# P-MT3620RDB-1-7_FTDI.net
KiCad netlist of a schematic drawn in Altium Designer
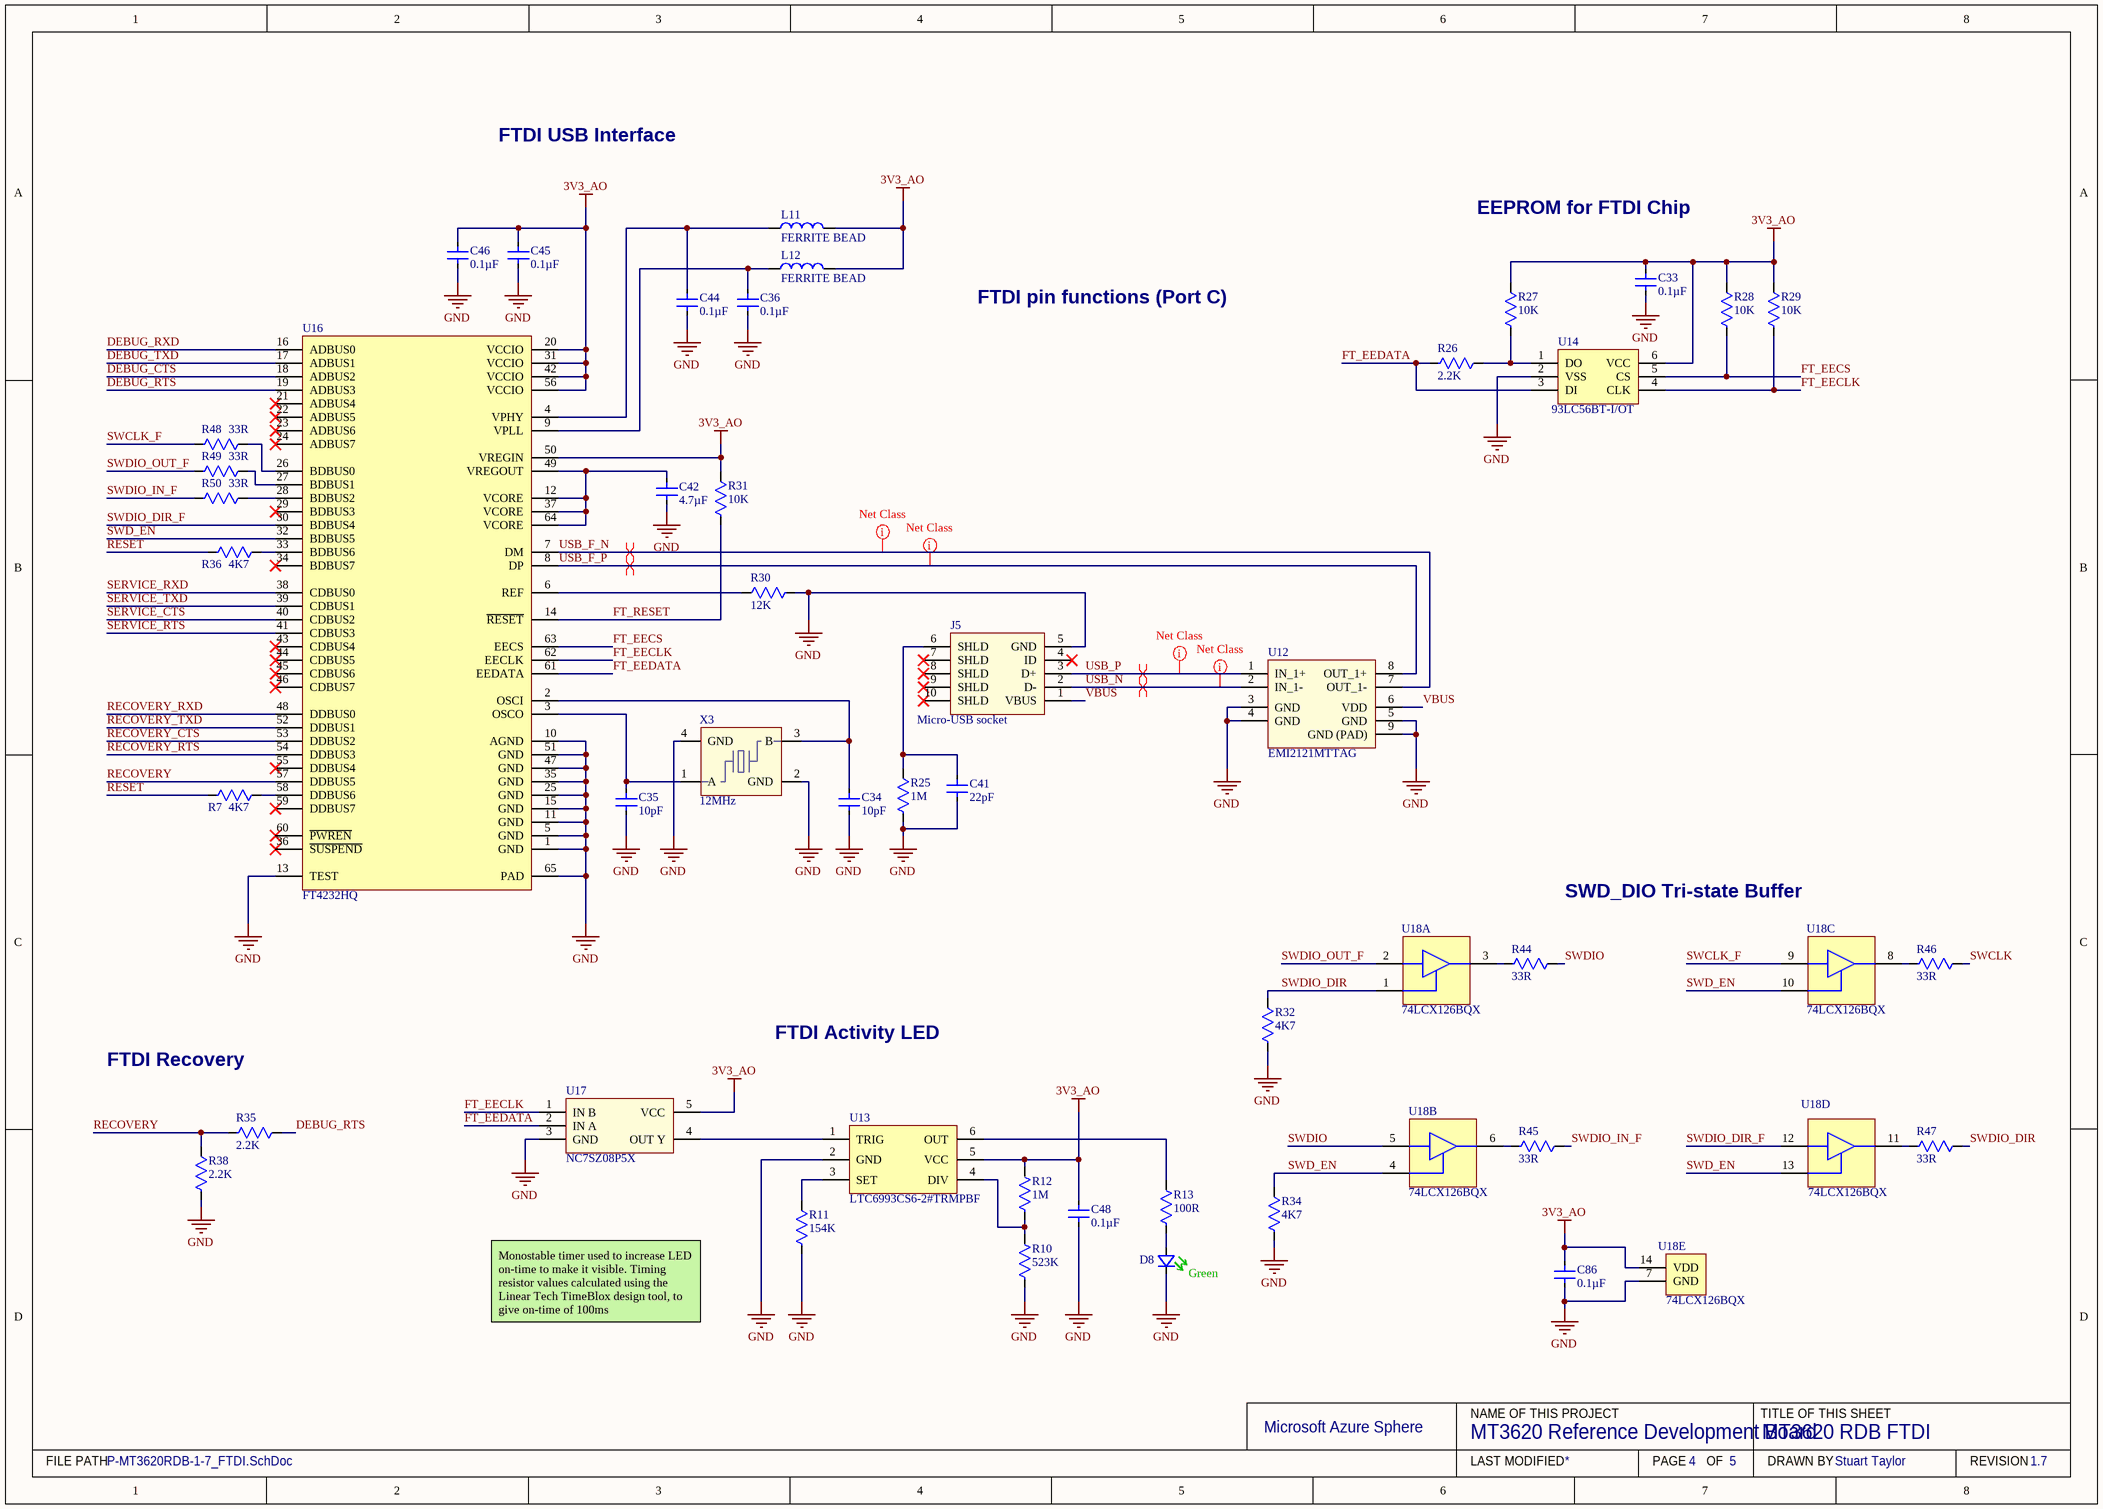
[diagram p0: P-MT3620RDB-1-7_FTDI.SchDoc]

(export (version "E")
  (design (tool "Eeschema 10.0.6"))
  (components
    (comp (ref "C33")
      (value "0.1µF")
      (footprint "CAPC1005-EIA0402 0.55MM MED")
      (description "CAP CER 0.1UF 50V 10% X7R 0402")
      (fields
        (field (name "MANUFACTURER") "TDK Corporation")
        (field (name "MANUFACTURER PART NUMBER") "C1005X7R1H104K050BB")
        (field (name "CAPACITANCE") "0.1µF")
      )
      (libsource (lib "TDK_Capacitor_C_0402") (part "0.1µF 0402 X7R 50V"))
    )
    (comp (ref "C34")
      (value "10pF")
      (footprint "CAPC1005-EIA0402 0.55MM MED")
      (description "CAP CER 10PF 50V NP0 0402")
      (fields
        (field (name "MANUFACTURER") "TDK Corporation")
        (field (name "MANUFACTURER PART NUMBER") "C1005C0G1H100D050BA")
        (field (name "CAPACITANCE") "10pF")
      )
      (libsource (lib "TDK_Capacitor_C_0402") (part "10pF 0402 C0G, NP0 50V"))
    )
    (comp (ref "C35")
      (value "10pF")
      (footprint "CAPC1005-EIA0402 0.55MM MED")
      (description "CAP CER 10PF 50V NP0 0402")
      (fields
        (field (name "MANUFACTURER") "TDK Corporation")
        (field (name "MANUFACTURER PART NUMBER") "C1005C0G1H100D050BA")
        (field (name "CAPACITANCE") "10pF")
      )
      (libsource (lib "TDK_Capacitor_C_0402") (part "10pF 0402 C0G, NP0 50V"))
    )
    (comp (ref "C36")
      (value "0.1µF")
      (footprint "CAPC1005-EIA0402 0.55MM MED")
      (description "CAP CER 0.1UF 50V 10% X7R 0402")
      (fields
        (field (name "MANUFACTURER") "TDK Corporation")
        (field (name "MANUFACTURER PART NUMBER") "C1005X7R1H104K050BB")
        (field (name "CAPACITANCE") "0.1µF")
      )
      (libsource (lib "TDK_Capacitor_C_0402") (part "0.1µF 0402 X7R 50V"))
    )
    (comp (ref "C41")
      (value "22pF")
      (footprint "CAPC1005-EIA0402 0.55MM MED")
      (description "CAP CER 22PF 50V 5% NP0 0402")
      (fields
        (field (name "MANUFACTURER") "TDK Corporation")
        (field (name "MANUFACTURER PART NUMBER") "C1005C0G1H220J050BA")
        (field (name "CAPACITANCE") "22pF")
      )
      (libsource (lib "TDK_Capacitor_C_0402") (part "22pF 0402 C0G, NP0 50V"))
    )
    (comp (ref "C42")
      (value "4.7µF")
      (footprint "CAPC1005-EIA0402 0.55MM MED")
      (description "CAP CER 4.7UF 10V 10% X5R 0402")
      (fields
        (field (name "MANUFACTURER") "TDK Corporation")
        (field (name "MANUFACTURER PART NUMBER") "C1005X5R1A475K050BC")
        (field (name "CAPACITANCE") "4.7µF")
      )
      (libsource (lib "TDK_Capacitor_C_0402") (part "4.7µF 0402 X5R 10V"))
    )
    (comp (ref "C44")
      (value "0.1µF")
      (footprint "CAPC1005-EIA0402 0.55MM MED")
      (description "CAP CER 0.1UF 50V 10% X7R 0402")
      (fields
        (field (name "MANUFACTURER") "TDK Corporation")
        (field (name "MANUFACTURER PART NUMBER") "C1005X7R1H104K050BB")
        (field (name "CAPACITANCE") "0.1µF")
      )
      (libsource (lib "TDK_Capacitor_C_0402") (part "0.1µF 0402 X7R 50V"))
    )
    (comp (ref "C45")
      (value "0.1µF")
      (footprint "CAPC1005-EIA0402 0.55MM MED")
      (description "CAP CER 0.1UF 50V 10% X7R 0402")
      (fields
        (field (name "MANUFACTURER") "TDK Corporation")
        (field (name "MANUFACTURER PART NUMBER") "C1005X7R1H104K050BB")
        (field (name "CAPACITANCE") "0.1µF")
      )
      (libsource (lib "TDK_Capacitor_C_0402") (part "0.1µF 0402 X7R 50V"))
    )
    (comp (ref "C46")
      (value "0.1µF")
      (footprint "CAPC1005-EIA0402 0.55MM MED")
      (description "CAP CER 0.1UF 50V 10% X7R 0402")
      (fields
        (field (name "MANUFACTURER") "TDK Corporation")
        (field (name "MANUFACTURER PART NUMBER") "C1005X7R1H104K050BB")
        (field (name "CAPACITANCE") "0.1µF")
      )
      (libsource (lib "TDK_Capacitor_C_0402") (part "0.1µF 0402 X7R 50V"))
    )
    (comp (ref "C48")
      (value "0.1µF")
      (footprint "CAPC1005-EIA0402 0.55MM MED")
      (description "CAP CER 0.1UF 50V 10% X7R 0402")
      (fields
        (field (name "MANUFACTURER") "TDK Corporation")
        (field (name "MANUFACTURER PART NUMBER") "C1005X7R1H104K050BB")
        (field (name "CAPACITANCE") "0.1µF")
      )
      (libsource (lib "TDK_Capacitor_C_0402") (part "0.1µF 0402 X7R 50V"))
    )
    (comp (ref "C86")
      (value "0.1µF")
      (footprint "CAPC1005-EIA0402 0.55MM MED")
      (description "CAP CER 0.1UF 50V 10% X7R 0402")
      (fields
        (field (name "MANUFACTURER") "TDK Corporation")
        (field (name "MANUFACTURER PART NUMBER") "C1005X7R1H104K050BB")
        (field (name "CAPACITANCE") "0.1µF")
      )
      (libsource (lib "TDK_Capacitor_C_0402") (part "0.1µF 0402 X7R 50V"))
    )
    (comp (ref "D8")
      (value "Green LED")
      (footprint "Rohm SML-D12 Green")
      (description "1.6 x 0.8 x 0.55mm (0603) LED 560nm Green")
      (fields
        (field (name "MANUFACTURER") "Rohm Semiconductor")
        (field (name "MANUFACTURER PART NUMBER") "SML-D12P8WT86")
        (field (name "COLOUR") "Green")
      )
      (libsource (lib "Rohm") (part "SML-D12P"))
    )
    (comp (ref "J5")
      (value "Micro-USB socket")
      (footprint "MCR-B-S-RA-SMT-CS5-T/R")
      (fields
        (field (name "MANUFACTURER") "Adam Tech")
        (field (name "MANUFACTURERS PART NUMBER") "MCR-B-S-RA-SMT-CS5-T/R")
      )
      (libsource (lib "AdamTech") (part "MCR-B-S-RA-SMT-CS5-T/R"))
    )
    (comp (ref "L11")
      (value "FERRITE BEAD")
      (footprint "CAPC1005-EIA0402 0.55MM MED")
      (description "FERRITE BEAD 120 OHM 0402 1LN")
      (fields
        (field (name "MANUFACTURER") "Murata Electronics North America")
        (field (name "MANUFACTURER PART NUMBER") "BLM15PD121SN1D")
      )
      (libsource (lib "Murata") (part "BLM15PD121SN1D"))
    )
    (comp (ref "L12")
      (value "FERRITE BEAD")
      (footprint "CAPC1005-EIA0402 0.55MM MED")
      (description "FERRITE BEAD 120 OHM 0402 1LN")
      (fields
        (field (name "MANUFACTURER") "Murata Electronics North America")
        (field (name "MANUFACTURER PART NUMBER") "BLM15PD121SN1D")
      )
      (libsource (lib "Murata") (part "BLM15PD121SN1D"))
    )
    (comp (ref "R7")
      (value "4K7")
      (footprint "RES 0402 MEDIUM DENSITY")
      (description "RES 4.7K OHM 1/10W 1% 0402 SMD")
      (fields
        (field (name "MANUFACTURER") "Panasonic Electronic Components")
        (field (name "MANUFACTURER PART NUMBER") "ERJ-2RKF4701X")
        (field (name "RESISTANCE (OHMS)") "4K7")
      )
      (libsource (lib "Panasonic_Resistor_ERJ2R") (part "4.7K"))
    )
    (comp (ref "R10")
      (value "523K")
      (footprint "RES 0402 MEDIUM DENSITY")
      (description "RES 523K OHM 1/10W 1% 0402 SMD")
      (fields
        (field (name "MANUFACTURER") "Panasonic Electronic Components")
        (field (name "MANUFACTURER PART NUMBER") "ERJ-2RKF5233X")
        (field (name "RESISTANCE (OHMS)") "523K")
      )
      (libsource (lib "Panasonic_Resistor_ERJ2R") (part "523K"))
    )
    (comp (ref "R11")
      (value "154K")
      (footprint "RES 0402 MEDIUM DENSITY")
      (description "RES 154K OHM 1/10W 1% 0402 SMD")
      (fields
        (field (name "MANUFACTURER") "Panasonic Electronic Components")
        (field (name "MANUFACTURER PART NUMBER") "ERJ-2RKF1543X")
        (field (name "RESISTANCE (OHMS)") "154K")
      )
      (libsource (lib "Panasonic_Resistor_ERJ2R") (part "154K"))
    )
    (comp (ref "R12")
      (value "1M")
      (footprint "RES 0402 MEDIUM DENSITY")
      (description "RES 1M OHM 1/10W 1% 0402 SMD")
      (fields
        (field (name "MANUFACTURER") "Panasonic Electronic Components")
        (field (name "MANUFACTURER PART NUMBER") "ERJ-2RKF1004X")
        (field (name "RESISTANCE (OHMS)") "1M")
      )
      (libsource (lib "Panasonic_Resistor_ERJ2R") (part "1M"))
    )
    (comp (ref "R13")
      (value "100R")
      (footprint "RES 0402 MEDIUM DENSITY")
      (description "RES 100 OHM 1/10W 1% 0402 SMD")
      (fields
        (field (name "MANUFACTURER") "Panasonic Electronic Components")
        (field (name "MANUFACTURER PART NUMBER") "ERJ-2RKF1000X")
        (field (name "RESISTANCE (OHMS)") "100R")
      )
      (libsource (lib "Panasonic_Resistor_ERJ2R") (part "100R"))
    )
    (comp (ref "R25")
      (value "1M")
      (footprint "RES 0402 MEDIUM DENSITY")
      (description "RES 1M OHM 1/10W 1% 0402 SMD")
      (fields
        (field (name "MANUFACTURER") "Panasonic Electronic Components")
        (field (name "MANUFACTURER PART NUMBER") "ERJ-2RKF1004X")
        (field (name "RESISTANCE (OHMS)") "1M")
      )
      (libsource (lib "Panasonic_Resistor_ERJ2R") (part "1M"))
    )
    (comp (ref "R26")
      (value "2.2K")
      (footprint "RES 0402 MEDIUM DENSITY")
      (description "RES 2.2K OHM 1/10W 1% 0402 SMD")
      (fields
        (field (name "MANUFACTURER") "Panasonic Electronic Components")
        (field (name "MANUFACTURER PART NUMBER") "ERJ-2RKF2201X")
        (field (name "RESISTANCE (OHMS)") "2.2K")
      )
      (libsource (lib "Panasonic_Resistor_ERJ2R") (part "2.2K"))
    )
    (comp (ref "R27")
      (value "10K")
      (footprint "RES 0402 MEDIUM DENSITY")
      (description "RES 10K OHM 1/10W 1% 0402 SMD")
      (fields
        (field (name "MANUFACTURER") "Panasonic Electronic Components")
        (field (name "MANUFACTURER PART NUMBER") "ERJ-2RKF1002X")
        (field (name "RESISTANCE (OHMS)") "10K")
      )
      (libsource (lib "Panasonic_Resistor_ERJ2R") (part "10K"))
    )
    (comp (ref "R28")
      (value "10K")
      (footprint "RES 0402 MEDIUM DENSITY")
      (description "RES 10K OHM 1/10W 1% 0402 SMD")
      (fields
        (field (name "MANUFACTURER") "Panasonic Electronic Components")
        (field (name "MANUFACTURER PART NUMBER") "ERJ-2RKF1002X")
        (field (name "RESISTANCE (OHMS)") "10K")
      )
      (libsource (lib "Panasonic_Resistor_ERJ2R") (part "10K"))
    )
    (comp (ref "R29")
      (value "10K")
      (footprint "RES 0402 MEDIUM DENSITY")
      (description "RES 10K OHM 1/10W 1% 0402 SMD")
      (fields
        (field (name "MANUFACTURER") "Panasonic Electronic Components")
        (field (name "MANUFACTURER PART NUMBER") "ERJ-2RKF1002X")
        (field (name "RESISTANCE (OHMS)") "10K")
      )
      (libsource (lib "Panasonic_Resistor_ERJ2R") (part "10K"))
    )
    (comp (ref "R30")
      (value "12K")
      (footprint "RES 0402 MEDIUM DENSITY")
      (description "RES 12K OHM 1/10W 1% 0402 SMD")
      (fields
        (field (name "MANUFACTURER") "Panasonic Electronic Components")
        (field (name "MANUFACTURER PART NUMBER") "ERJ-2RKF1202X")
        (field (name "RESISTANCE (OHMS)") "12K")
      )
      (libsource (lib "Panasonic_Resistor_ERJ2R") (part "12K"))
    )
    (comp (ref "R31")
      (value "10K")
      (footprint "RES 0402 MEDIUM DENSITY")
      (description "RES 10K OHM 1/10W 1% 0402 SMD")
      (fields
        (field (name "MANUFACTURER") "Panasonic Electronic Components")
        (field (name "MANUFACTURER PART NUMBER") "ERJ-2RKF1002X")
        (field (name "RESISTANCE (OHMS)") "10K")
      )
      (libsource (lib "Panasonic_Resistor_ERJ2R") (part "10K"))
    )
    (comp (ref "R32")
      (value "4K7")
      (footprint "RES 0402 MEDIUM DENSITY")
      (description "RES 4.7K OHM 1/10W 1% 0402 SMD")
      (fields
        (field (name "MANUFACTURER") "Panasonic Electronic Components")
        (field (name "MANUFACTURER PART NUMBER") "ERJ-2RKF4701X")
        (field (name "RESISTANCE (OHMS)") "4K7")
      )
      (libsource (lib "Panasonic_Resistor_ERJ2R") (part "4.7K"))
    )
    (comp (ref "R34")
      (value "4K7")
      (footprint "RES 0402 MEDIUM DENSITY")
      (description "RES 4.7K OHM 1/10W 1% 0402 SMD")
      (fields
        (field (name "MANUFACTURER") "Panasonic Electronic Components")
        (field (name "MANUFACTURER PART NUMBER") "ERJ-2RKF4701X")
        (field (name "RESISTANCE (OHMS)") "4K7")
      )
      (libsource (lib "Panasonic_Resistor_ERJ2R") (part "4.7K"))
    )
    (comp (ref "R35")
      (value "2.2K")
      (footprint "RES 0402 MEDIUM DENSITY")
      (description "RES 2.2K OHM 1/10W 1% 0402 SMD")
      (fields
        (field (name "MANUFACTURER") "Panasonic Electronic Components")
        (field (name "MANUFACTURER PART NUMBER") "ERJ-2RKF2201X")
        (field (name "RESISTANCE (OHMS)") "2.2K")
      )
      (libsource (lib "Panasonic_Resistor_ERJ2R") (part "2.2K"))
    )
    (comp (ref "R36")
      (value "4K7")
      (footprint "RES 0402 MEDIUM DENSITY")
      (description "RES 4.7K OHM 1/10W 1% 0402 SMD")
      (fields
        (field (name "MANUFACTURER") "Panasonic Electronic Components")
        (field (name "MANUFACTURER PART NUMBER") "ERJ-2RKF4701X")
        (field (name "RESISTANCE (OHMS)") "4K7")
      )
      (libsource (lib "Panasonic_Resistor_ERJ2R") (part "4.7K"))
    )
    (comp (ref "R38")
      (value "2.2K")
      (footprint "RES 0402 MEDIUM DENSITY")
      (description "RES 2.2K OHM 1/10W 1% 0402 SMD")
      (fields
        (field (name "MANUFACTURER") "Panasonic Electronic Components")
        (field (name "MANUFACTURER PART NUMBER") "ERJ-2RKF2201X")
        (field (name "RESISTANCE (OHMS)") "2.2K")
      )
      (libsource (lib "Panasonic_Resistor_ERJ2R") (part "2.2K"))
    )
    (comp (ref "R44")
      (value "33R")
      (footprint "RES 0402 MEDIUM DENSITY")
      (description "RES 33 OHM 1/10W 1% 0402 SMD")
      (fields
        (field (name "MANUFACTURER") "Panasonic Electronic Components")
        (field (name "MANUFACTURER PART NUMBER") "ERJ-2RKF33R0X")
        (field (name "RESISTANCE (OHMS)") "33R")
      )
      (libsource (lib "Panasonic_Resistor_ERJ2R") (part "33R"))
    )
    (comp (ref "R45")
      (value "33R")
      (footprint "RES 0402 MEDIUM DENSITY")
      (description "RES 33 OHM 1/10W 1% 0402 SMD")
      (fields
        (field (name "MANUFACTURER") "Panasonic Electronic Components")
        (field (name "MANUFACTURER PART NUMBER") "ERJ-2RKF33R0X")
        (field (name "RESISTANCE (OHMS)") "33R")
      )
      (libsource (lib "Panasonic_Resistor_ERJ2R") (part "33R"))
    )
    (comp (ref "R46")
      (value "33R")
      (footprint "RES 0402 MEDIUM DENSITY")
      (description "RES 33 OHM 1/10W 1% 0402 SMD")
      (fields
        (field (name "MANUFACTURER") "Panasonic Electronic Components")
        (field (name "MANUFACTURER PART NUMBER") "ERJ-2RKF33R0X")
        (field (name "RESISTANCE (OHMS)") "33R")
      )
      (libsource (lib "Panasonic_Resistor_ERJ2R") (part "33R"))
    )
    (comp (ref "R47")
      (value "33R")
      (footprint "RES 0402 MEDIUM DENSITY")
      (description "RES 33 OHM 1/10W 1% 0402 SMD")
      (fields
        (field (name "MANUFACTURER") "Panasonic Electronic Components")
        (field (name "MANUFACTURER PART NUMBER") "ERJ-2RKF33R0X")
        (field (name "RESISTANCE (OHMS)") "33R")
      )
      (libsource (lib "Panasonic_Resistor_ERJ2R") (part "33R"))
    )
    (comp (ref "R48")
      (value "33R")
      (footprint "RES 0402 MEDIUM DENSITY")
      (description "RES 33 OHM 1/10W 1% 0402 SMD")
      (fields
        (field (name "MANUFACTURER") "Panasonic Electronic Components")
        (field (name "MANUFACTURER PART NUMBER") "ERJ-2RKF33R0X")
        (field (name "RESISTANCE (OHMS)") "33R")
      )
      (libsource (lib "Panasonic_Resistor_ERJ2R") (part "33R"))
    )
    (comp (ref "R49")
      (value "33R")
      (footprint "RES 0402 MEDIUM DENSITY")
      (description "RES 33 OHM 1/10W 1% 0402 SMD")
      (fields
        (field (name "MANUFACTURER") "Panasonic Electronic Components")
        (field (name "MANUFACTURER PART NUMBER") "ERJ-2RKF33R0X")
        (field (name "RESISTANCE (OHMS)") "33R")
      )
      (libsource (lib "Panasonic_Resistor_ERJ2R") (part "33R"))
    )
    (comp (ref "R50")
      (value "33R")
      (footprint "RES 0402 MEDIUM DENSITY")
      (description "RES 33 OHM 1/10W 1% 0402 SMD")
      (fields
        (field (name "MANUFACTURER") "Panasonic Electronic Components")
        (field (name "MANUFACTURER PART NUMBER") "ERJ-2RKF33R0X")
        (field (name "RESISTANCE (OHMS)") "33R")
      )
      (libsource (lib "Panasonic_Resistor_ERJ2R") (part "33R"))
    )
    (comp (ref "U12")
      (value "EMI2121MTTAG")
      (footprint "EMI2121MTTAG")
      (description "IC FILTER COMMON MODE ESD 8WDFN")
      (fields (field (name "MANUFACTURER") "ON Semiconductor"))
      (libsource (lib "OnSemiconductor") (part "EMI2121MTTAG"))
    )
    (comp (ref "U13")
      (value "LTC6993CS6-2#TRMPBF")
      (footprint "LTC6993CS6-2#TRMPBF")
      (description "LINEAR TECHNOLOGY - LTC6993CS6-2#TRMPBF - GENERATOR, PULSE, TIMERBLOX, 6SOT-23")
      (fields (field (name "MANUFACTURER") "LINEAR TECHNOLOGY"))
      (libsource (lib "LinearTech") (part "LTC6993CS6-2#TRMPBF"))
    )
    (comp (ref "U14")
      (value "93LC56BT-I/OT")
      (footprint "SOT23-93C56B")
      (description "IC EEPROM 2KBIT 2MHZ SOT23-6")
      (fields (field (name "MANUFACTURER") "Microchip Technology"))
      (libsource (lib "Microchip") (part "93LC56BT-I/OT"))
    )
    (comp (ref "U16")
      (value "FT4232HQ")
      (footprint "FTDI_TF4232HQ_64QFN")
      (description "IC USB HS QUAD UART/SYNC 64-QFN")
      (fields
        (field (name "MANUFACTURER") "FTDI, Future Technology Devices International Ltd")
        (field (name "MANUFACTURER PART NUMBER") "FT4232HQ-REEL")
      )
      (libsource (lib "FTDI") (part "FT4232HQ"))
    )
    (comp (ref "U17")
      (value "NC7SZ08P5X")
      (footprint "SC-70-5")
      (description "IC GATE AND 1CH 2-INP SC-70-5")
      (fields (field (name "MANUFACTURER") "Fairchild Semiconductor"))
      (libsource (lib "OnSemiconductor") (part "NC7SZ08P5X"))
    )
    (comp (ref "U18")
      (value "74LCX126BQX")
      (footprint "74LCX126BQX")
      (description "IC BUFFER QUAD LV N-INV 14DQFN")
      (fields (field (name "MANUFACTURER") "Fairchild Semiconductor"))
      (libsource (lib "OnSemiconductor") (part "74LCX126BQX"))
    )
    (comp (ref "X3")
      (value "12MHz")
      (footprint "TXC 8Z")
      (description "CRYSTAL 12.000 MHZ 18PF SMD")
      (fields
        (field (name "MANUFACTURER") "TXC CORPORATION")
        (field (name "MANUFACTURER PART NUMBER") "8Z-12.000MAAJ-T")
        (field (name "FREQUENCY") "12MHz")
      )
      (libsource (lib "crystal") (part "CRYSTAL 12MHz 18pF SMD"))
    )
  )
  (nets
    (net (code "1") (name "/DEBUG_CTS") (class "Default")
      (node (ref "U16") (pin "18") (pinfunction "ADBUS2_18") (pintype "passive"))
    )
    (net (code "2") (name "/DEBUG_RTS") (class "Default")
      (node (ref "R35") (pin "1") (pinfunction "1_1") (pintype "passive"))
      (node (ref "U16") (pin "19") (pinfunction "ADBUS3_19") (pintype "passive"))
    )
    (net (code "3") (name "/DEBUG_RXD") (class "Default")
      (node (ref "U16") (pin "16") (pinfunction "ADBUS0_16") (pintype "passive"))
    )
    (net (code "4") (name "/DEBUG_TXD") (class "Default")
      (node (ref "U16") (pin "17") (pinfunction "ADBUS1_17") (pintype "passive"))
    )
    (net (code "5") (name "/FT_EECLK") (class "Default")
      (node (ref "R29") (pin "2") (pinfunction "2_2") (pintype "passive"))
      (node (ref "U14") (pin "4") (pinfunction "CLK_4") (pintype "passive"))
      (node (ref "U16") (pin "62") (pinfunction "EECLK_62") (pintype "passive"))
      (node (ref "U17") (pin "1") (pinfunction "IN_B_1") (pintype "passive"))
    )
    (net (code "6") (name "/FT_EECS") (class "Default")
      (node (ref "R28") (pin "2") (pinfunction "2_2") (pintype "passive"))
      (node (ref "U14") (pin "5") (pinfunction "CS_5") (pintype "passive"))
      (node (ref "U16") (pin "63") (pinfunction "EECS_63") (pintype "passive"))
    )
    (net (code "7") (name "/FT_EEDATA") (class "Default")
      (node (ref "R26") (pin "2") (pinfunction "2_2") (pintype "passive"))
      (node (ref "U14") (pin "3") (pinfunction "DI_3") (pintype "passive"))
      (node (ref "U16") (pin "61") (pinfunction "EEDATA_61") (pintype "passive"))
      (node (ref "U17") (pin "2") (pinfunction "IN_A_2") (pintype "passive"))
    )
    (net (code "8") (name "/FT_RESET") (class "Default")
      (node (ref "R31") (pin "2") (pinfunction "2_2") (pintype "passive"))
      (node (ref "U16") (pin "14") (pinfunction "~{RESET}_14") (pintype "passive"))
    )
    (net (code "9") (name "/RECOVERY") (class "Default")
      (node (ref "R35") (pin "2") (pinfunction "2_2") (pintype "passive"))
      (node (ref "R38") (pin "1") (pinfunction "1_1") (pintype "passive"))
      (node (ref "U16") (pin "57") (pinfunction "DDBUS5_57") (pintype "passive"))
    )
    (net (code "10") (name "/RECOVERY_CTS") (class "Default")
      (node (ref "U16") (pin "53") (pinfunction "DDBUS2_53") (pintype "passive"))
    )
    (net (code "11") (name "/RECOVERY_RTS") (class "Default")
      (node (ref "U16") (pin "54") (pinfunction "DDBUS3_54") (pintype "passive"))
    )
    (net (code "12") (name "/RECOVERY_RXD") (class "Default")
      (node (ref "U16") (pin "48") (pinfunction "DDBUS0_48") (pintype "passive"))
    )
    (net (code "13") (name "/RECOVERY_TXD") (class "Default")
      (node (ref "U16") (pin "52") (pinfunction "DDBUS1_52") (pintype "passive"))
    )
    (net (code "14") (name "/RESET") (class "Default")
      (node (ref "R36") (pin "2") (pinfunction "2_2") (pintype "passive"))
      (node (ref "R7") (pin "2") (pinfunction "2_2") (pintype "passive"))
    )
    (net (code "15") (name "/SERVICE_CTS") (class "Default")
      (node (ref "U16") (pin "40") (pinfunction "CDBUS2_40") (pintype "passive"))
    )
    (net (code "16") (name "/SERVICE_RTS") (class "Default")
      (node (ref "U16") (pin "41") (pinfunction "CDBUS3_41") (pintype "passive"))
    )
    (net (code "17") (name "/SERVICE_RXD") (class "Default")
      (node (ref "U16") (pin "38") (pinfunction "CDBUS0_38") (pintype "passive"))
    )
    (net (code "18") (name "/SERVICE_TXD") (class "Default")
      (node (ref "U16") (pin "39") (pinfunction "CDBUS1_39") (pintype "passive"))
    )
    (net (code "19") (name "/SWCLK") (class "Default")
      (node (ref "R46") (pin "1") (pinfunction "1_1") (pintype "passive"))
    )
    (net (code "20") (name "/SWCLK_F") (class "Default")
      (node (ref "R48") (pin "2") (pinfunction "2_2") (pintype "passive"))
      (node (ref "U18") (pin "9") (pinfunction "3A_9") (pintype "passive"))
    )
    (net (code "21") (name "/SWDIO") (class "Default")
      (node (ref "R44") (pin "1") (pinfunction "1_1") (pintype "passive"))
      (node (ref "U18") (pin "5") (pinfunction "2A_5") (pintype "passive"))
    )
    (net (code "22") (name "/SWDIO_DIR") (class "Default")
      (node (ref "R32") (pin "1") (pinfunction "1_1") (pintype "passive"))
      (node (ref "R47") (pin "1") (pinfunction "1_1") (pintype "passive"))
      (node (ref "U18") (pin "1") (pinfunction "1OE_1") (pintype "passive"))
    )
    (net (code "23") (name "/SWDIO_DIR_F") (class "Default")
      (node (ref "U16") (pin "30") (pinfunction "BDBUS4_30") (pintype "passive"))
      (node (ref "U18") (pin "12") (pinfunction "4A_12") (pintype "passive"))
    )
    (net (code "24") (name "/SWDIO_IN_F") (class "Default")
      (node (ref "R45") (pin "1") (pinfunction "1_1") (pintype "passive"))
      (node (ref "R50") (pin "2") (pinfunction "2_2") (pintype "passive"))
    )
    (net (code "25") (name "/SWDIO_OUT_F") (class "Default")
      (node (ref "R49") (pin "2") (pinfunction "2_2") (pintype "passive"))
      (node (ref "U18") (pin "2") (pinfunction "1A_2") (pintype "passive"))
    )
    (net (code "26") (name "/SWD_EN") (class "Default")
      (node (ref "R34") (pin "1") (pinfunction "1_1") (pintype "passive"))
      (node (ref "U16") (pin "32") (pinfunction "BDBUS5_32") (pintype "passive"))
      (node (ref "U18") (pin "10") (pinfunction "3OE_10") (pintype "passive"))
      (node (ref "U18") (pin "13") (pinfunction "4OE_13") (pintype "passive"))
      (node (ref "U18") (pin "4") (pinfunction "2OE_4") (pintype "passive"))
    )
    (net (code "27") (name "/USB_F_N") (class "Default")
      (node (ref "U12") (pin "7") (pinfunction "OUT_1-_7") (pintype "passive"))
      (node (ref "U16") (pin "7") (pinfunction "DM_7") (pintype "passive"))
    )
    (net (code "28") (name "/USB_F_P") (class "Default")
      (node (ref "U12") (pin "8") (pinfunction "OUT_1+_8") (pintype "passive"))
      (node (ref "U16") (pin "8") (pinfunction "DP_8") (pintype "passive"))
    )
    (net (code "29") (name "/USB_N") (class "Default")
      (node (ref "J5") (pin "2") (pinfunction "D-_2") (pintype "passive"))
      (node (ref "U12") (pin "2") (pinfunction "IN_1-_2") (pintype "passive"))
    )
    (net (code "30") (name "/USB_P") (class "Default")
      (node (ref "J5") (pin "3") (pinfunction "D+_3") (pintype "passive"))
      (node (ref "U12") (pin "1") (pinfunction "IN_1+_1") (pintype "passive"))
    )
    (net (code "31") (name "/VBUS") (class "Default")
      (node (ref "J5") (pin "1") (pinfunction "VBUS_1") (pintype "passive"))
      (node (ref "U12") (pin "6") (pinfunction "VDD_6") (pintype "passive"))
    )
    (net (code "32") (name "3V3_AO") (class "Default")
      (node (ref "C33") (pin "2") (pinfunction "2_2") (pintype "passive"))
      (node (ref "C45") (pin "2") (pinfunction "2_2") (pintype "passive"))
      (node (ref "C46") (pin "2") (pinfunction "2_2") (pintype "passive"))
      (node (ref "C48") (pin "2") (pinfunction "2_2") (pintype "passive"))
      (node (ref "C86") (pin "2") (pinfunction "2_2") (pintype "passive"))
      (node (ref "L11") (pin "2") (pinfunction "2_2") (pintype "passive"))
      (node (ref "L12") (pin "2") (pinfunction "2_2") (pintype "passive"))
      (node (ref "R12") (pin "1") (pinfunction "1_1") (pintype "passive"))
      (node (ref "R27") (pin "1") (pinfunction "1_1") (pintype "passive"))
      (node (ref "R28") (pin "1") (pinfunction "1_1") (pintype "passive"))
      (node (ref "R29") (pin "1") (pinfunction "1_1") (pintype "passive"))
      (node (ref "R31") (pin "1") (pinfunction "1_1") (pintype "passive"))
      (node (ref "U13") (pin "5") (pinfunction "VCC_5") (pintype "passive"))
      (node (ref "U14") (pin "6") (pinfunction "VCC_6") (pintype "passive"))
      (node (ref "U16") (pin "20") (pinfunction "VCCIO_20") (pintype "passive"))
      (node (ref "U16") (pin "31") (pinfunction "VCCIO_31") (pintype "passive"))
      (node (ref "U16") (pin "42") (pinfunction "VCCIO_42") (pintype "passive"))
      (node (ref "U16") (pin "50") (pinfunction "VREGIN_50") (pintype "passive"))
      (node (ref "U16") (pin "56") (pinfunction "VCCIO_56") (pintype "passive"))
      (node (ref "U17") (pin "5") (pinfunction "VCC_5") (pintype "passive"))
      (node (ref "U18") (pin "14") (pinfunction "VDD_14") (pintype "passive"))
    )
    (net (code "33") (name "GND") (class "Default")
      (node (ref "C33") (pin "1") (pinfunction "1_1") (pintype "passive"))
      (node (ref "C34") (pin "1") (pinfunction "1_1") (pintype "passive"))
      (node (ref "C35") (pin "1") (pinfunction "1_1") (pintype "passive"))
      (node (ref "C36") (pin "1") (pinfunction "1_1") (pintype "passive"))
      (node (ref "C41") (pin "1") (pinfunction "1_1") (pintype "passive"))
      (node (ref "C42") (pin "1") (pinfunction "1_1") (pintype "passive"))
      (node (ref "C44") (pin "1") (pinfunction "1_1") (pintype "passive"))
      (node (ref "C45") (pin "1") (pinfunction "1_1") (pintype "passive"))
      (node (ref "C46") (pin "1") (pinfunction "1_1") (pintype "passive"))
      (node (ref "C48") (pin "1") (pinfunction "1_1") (pintype "passive"))
      (node (ref "C86") (pin "1") (pinfunction "1_1") (pintype "passive"))
      (node (ref "D8") (pin "1") (pinfunction "K_1") (pintype "passive"))
      (node (ref "J5") (pin "5") (pinfunction "GND_5") (pintype "passive"))
      (node (ref "R10") (pin "2") (pinfunction "2_2") (pintype "passive"))
      (node (ref "R11") (pin "2") (pinfunction "2_2") (pintype "passive"))
      (node (ref "R25") (pin "2") (pinfunction "2_2") (pintype "passive"))
      (node (ref "R30") (pin "2") (pinfunction "2_2") (pintype "passive"))
      (node (ref "R32") (pin "2") (pinfunction "2_2") (pintype "passive"))
      (node (ref "R34") (pin "2") (pinfunction "2_2") (pintype "passive"))
      (node (ref "R38") (pin "2") (pinfunction "2_2") (pintype "passive"))
      (node (ref "U12") (pin "3") (pinfunction "GND_3") (pintype "passive"))
      (node (ref "U12") (pin "4") (pinfunction "GND_4") (pintype "passive"))
      (node (ref "U12") (pin "5") (pinfunction "GND_5") (pintype "passive"))
      (node (ref "U12") (pin "9") (pinfunction "GND_(PAD)_9") (pintype "passive"))
      (node (ref "U13") (pin "2") (pinfunction "GND_2") (pintype "passive"))
      (node (ref "U14") (pin "2") (pinfunction "VSS_2") (pintype "passive"))
      (node (ref "U16") (pin "1") (pinfunction "GND_1") (pintype "passive"))
      (node (ref "U16") (pin "10") (pinfunction "AGND_10") (pintype "passive"))
      (node (ref "U16") (pin "11") (pinfunction "GND_11") (pintype "passive"))
      (node (ref "U16") (pin "13") (pinfunction "TEST_13") (pintype "passive"))
      (node (ref "U16") (pin "15") (pinfunction "GND_15") (pintype "passive"))
      (node (ref "U16") (pin "25") (pinfunction "GND_25") (pintype "passive"))
      (node (ref "U16") (pin "35") (pinfunction "GND_35") (pintype "passive"))
      (node (ref "U16") (pin "47") (pinfunction "GND_47") (pintype "passive"))
      (node (ref "U16") (pin "5") (pinfunction "GND_5") (pintype "passive"))
      (node (ref "U16") (pin "51") (pinfunction "GND_51") (pintype "passive"))
      (node (ref "U16") (pin "65") (pinfunction "PAD_65") (pintype "passive"))
      (node (ref "U17") (pin "3") (pinfunction "GND_3") (pintype "passive"))
      (node (ref "U18") (pin "7") (pinfunction "GND_7") (pintype "passive"))
      (node (ref "X3") (pin "2") (pinfunction "GND_2") (pintype "passive"))
      (node (ref "X3") (pin "4") (pinfunction "GND_4") (pintype "passive"))
    )
    (net (code "34") (name "Net-(C41-Pad2)") (class "Default")
      (node (ref "C41") (pin "2") (pinfunction "2_2") (pintype "passive"))
      (node (ref "J5") (pin "6") (pinfunction "SHLD_6") (pintype "passive"))
      (node (ref "R25") (pin "1") (pinfunction "1_1") (pintype "passive"))
    )
    (net (code "35") (name "Net-(D8-A)") (class "Default")
      (node (ref "D8") (pin "2") (pinfunction "A_2") (pintype "passive"))
      (node (ref "R13") (pin "2") (pinfunction "2_2") (pintype "passive"))
    )
    (net (code "36") (name "Net-(U13-DIV)") (class "Default")
      (node (ref "R10") (pin "1") (pinfunction "1_1") (pintype "passive"))
      (node (ref "R12") (pin "2") (pinfunction "2_2") (pintype "passive"))
      (node (ref "U13") (pin "4") (pinfunction "DIV_4") (pintype "passive"))
    )
    (net (code "37") (name "Net-(U13-OUT)") (class "Default")
      (node (ref "R13") (pin "1") (pinfunction "1_1") (pintype "passive"))
      (node (ref "U13") (pin "6") (pinfunction "OUT_6") (pintype "passive"))
    )
    (net (code "38") (name "Net-(U13-SET)") (class "Default")
      (node (ref "R11") (pin "1") (pinfunction "1_1") (pintype "passive"))
      (node (ref "U13") (pin "3") (pinfunction "SET_3") (pintype "passive"))
    )
    (net (code "39") (name "Net-(U13-TRIG)") (class "Default")
      (node (ref "U13") (pin "1") (pinfunction "TRIG_1") (pintype "passive"))
      (node (ref "U17") (pin "4") (pinfunction "OUT_Y_4") (pintype "passive"))
    )
    (net (code "40") (name "Net-(U14-DO)") (class "Default")
      (node (ref "R26") (pin "1") (pinfunction "1_1") (pintype "passive"))
      (node (ref "R27") (pin "2") (pinfunction "2_2") (pintype "passive"))
      (node (ref "U14") (pin "1") (pinfunction "DO_1") (pintype "passive"))
    )
    (net (code "41") (name "Net-(U16-BDBUS0)") (class "Default")
      (node (ref "R48") (pin "1") (pinfunction "1_1") (pintype "passive"))
      (node (ref "U16") (pin "26") (pinfunction "BDBUS0_26") (pintype "passive"))
    )
    (net (code "42") (name "Net-(U16-BDBUS1)") (class "Default")
      (node (ref "R49") (pin "1") (pinfunction "1_1") (pintype "passive"))
      (node (ref "U16") (pin "27") (pinfunction "BDBUS1_27") (pintype "passive"))
    )
    (net (code "43") (name "Net-(U16-BDBUS2)") (class "Default")
      (node (ref "R50") (pin "1") (pinfunction "1_1") (pintype "passive"))
      (node (ref "U16") (pin "28") (pinfunction "BDBUS2_28") (pintype "passive"))
    )
    (net (code "44") (name "Net-(U16-BDBUS6)") (class "Default")
      (node (ref "R36") (pin "1") (pinfunction "1_1") (pintype "passive"))
      (node (ref "U16") (pin "33") (pinfunction "BDBUS6_33") (pintype "passive"))
    )
    (net (code "45") (name "Net-(U16-DDBUS6)") (class "Default")
      (node (ref "R7") (pin "1") (pinfunction "1_1") (pintype "passive"))
      (node (ref "U16") (pin "58") (pinfunction "DDBUS6_58") (pintype "passive"))
    )
    (net (code "46") (name "Net-(U16-OSCI)") (class "Default")
      (node (ref "C34") (pin "2") (pinfunction "2_2") (pintype "passive"))
      (node (ref "U16") (pin "2") (pinfunction "OSCI_2") (pintype "passive"))
      (node (ref "X3") (pin "3") (pinfunction "B_3") (pintype "passive"))
    )
    (net (code "47") (name "Net-(U16-OSCO)") (class "Default")
      (node (ref "C35") (pin "2") (pinfunction "2_2") (pintype "passive"))
      (node (ref "U16") (pin "3") (pinfunction "OSCO_3") (pintype "passive"))
      (node (ref "X3") (pin "1") (pinfunction "A_1") (pintype "passive"))
    )
    (net (code "48") (name "Net-(U16-REF)") (class "Default")
      (node (ref "R30") (pin "1") (pinfunction "1_1") (pintype "passive"))
      (node (ref "U16") (pin "6") (pinfunction "REF_6") (pintype "passive"))
    )
    (net (code "49") (name "Net-(U16-VPHY)") (class "Default")
      (node (ref "C44") (pin "2") (pinfunction "2_2") (pintype "passive"))
      (node (ref "L11") (pin "1") (pinfunction "1_1") (pintype "passive"))
      (node (ref "U16") (pin "4") (pinfunction "VPHY_4") (pintype "passive"))
    )
    (net (code "50") (name "Net-(U16-VPLL)") (class "Default")
      (node (ref "C36") (pin "2") (pinfunction "2_2") (pintype "passive"))
      (node (ref "L12") (pin "1") (pinfunction "1_1") (pintype "passive"))
      (node (ref "U16") (pin "9") (pinfunction "VPLL_9") (pintype "passive"))
    )
    (net (code "51") (name "Net-(U16-VREGOUT)") (class "Default")
      (node (ref "C42") (pin "2") (pinfunction "2_2") (pintype "passive"))
      (node (ref "U16") (pin "12") (pinfunction "VCORE_12") (pintype "passive"))
      (node (ref "U16") (pin "37") (pinfunction "VCORE_37") (pintype "passive"))
      (node (ref "U16") (pin "49") (pinfunction "VREGOUT_49") (pintype "passive"))
      (node (ref "U16") (pin "64") (pinfunction "VCORE_64") (pintype "passive"))
    )
    (net (code "52") (name "Net-(U18A-1Y)") (class "Default")
      (node (ref "R44") (pin "2") (pinfunction "2_2") (pintype "passive"))
      (node (ref "U18") (pin "3") (pinfunction "1Y_3") (pintype "passive"))
    )
    (net (code "53") (name "Net-(U18B-2Y)") (class "Default")
      (node (ref "R45") (pin "2") (pinfunction "2_2") (pintype "passive"))
      (node (ref "U18") (pin "6") (pinfunction "2Y_6") (pintype "passive"))
    )
    (net (code "54") (name "Net-(U18C-3Y)") (class "Default")
      (node (ref "R46") (pin "2") (pinfunction "2_2") (pintype "passive"))
      (node (ref "U18") (pin "8") (pinfunction "3Y_8") (pintype "passive"))
    )
    (net (code "55") (name "Net-(U18D-4Y)") (class "Default")
      (node (ref "R47") (pin "2") (pinfunction "2_2") (pintype "passive"))
      (node (ref "U18") (pin "11") (pinfunction "4Y_11") (pintype "passive"))
    )
    (net (code "56") (name "unconnected-(J5-ID-Pad4)") (class "Default")
      (node (ref "J5") (pin "4") (pinfunction "ID_4") (pintype "passive+no_connect"))
    )
    (net (code "57") (name "unconnected-(J5-SHLD-Pad7)") (class "Default")
      (node (ref "J5") (pin "7") (pinfunction "SHLD_7") (pintype "passive+no_connect"))
    )
    (net (code "58") (name "unconnected-(J5-SHLD-Pad8)") (class "Default")
      (node (ref "J5") (pin "8") (pinfunction "SHLD_8") (pintype "passive+no_connect"))
    )
    (net (code "59") (name "unconnected-(J5-SHLD-Pad9)") (class "Default")
      (node (ref "J5") (pin "9") (pinfunction "SHLD_9") (pintype "passive+no_connect"))
    )
    (net (code "60") (name "unconnected-(J5-SHLD-Pad10)") (class "Default")
      (node (ref "J5") (pin "10") (pinfunction "SHLD_10") (pintype "passive+no_connect"))
    )
    (net (code "61") (name "unconnected-(U16-ADBUS4-Pad21)") (class "Default")
      (node (ref "U16") (pin "21") (pinfunction "ADBUS4_21") (pintype "passive+no_connect"))
    )
    (net (code "62") (name "unconnected-(U16-ADBUS5-Pad22)") (class "Default")
      (node (ref "U16") (pin "22") (pinfunction "ADBUS5_22") (pintype "passive+no_connect"))
    )
    (net (code "63") (name "unconnected-(U16-ADBUS6-Pad23)") (class "Default")
      (node (ref "U16") (pin "23") (pinfunction "ADBUS6_23") (pintype "passive+no_connect"))
    )
    (net (code "64") (name "unconnected-(U16-ADBUS7-Pad24)") (class "Default")
      (node (ref "U16") (pin "24") (pinfunction "ADBUS7_24") (pintype "passive+no_connect"))
    )
    (net (code "65") (name "unconnected-(U16-BDBUS3-Pad29)") (class "Default")
      (node (ref "U16") (pin "29") (pinfunction "BDBUS3_29") (pintype "passive+no_connect"))
    )
    (net (code "66") (name "unconnected-(U16-BDBUS7-Pad34)") (class "Default")
      (node (ref "U16") (pin "34") (pinfunction "BDBUS7_34") (pintype "passive+no_connect"))
    )
    (net (code "67") (name "unconnected-(U16-CDBUS4-Pad43)") (class "Default")
      (node (ref "U16") (pin "43") (pinfunction "CDBUS4_43") (pintype "passive+no_connect"))
    )
    (net (code "68") (name "unconnected-(U16-CDBUS5-Pad44)") (class "Default")
      (node (ref "U16") (pin "44") (pinfunction "CDBUS5_44") (pintype "passive+no_connect"))
    )
    (net (code "69") (name "unconnected-(U16-CDBUS6-Pad45)") (class "Default")
      (node (ref "U16") (pin "45") (pinfunction "CDBUS6_45") (pintype "passive+no_connect"))
    )
    (net (code "70") (name "unconnected-(U16-CDBUS7-Pad46)") (class "Default")
      (node (ref "U16") (pin "46") (pinfunction "CDBUS7_46") (pintype "passive+no_connect"))
    )
    (net (code "71") (name "unconnected-(U16-DDBUS4-Pad55)") (class "Default")
      (node (ref "U16") (pin "55") (pinfunction "DDBUS4_55") (pintype "passive+no_connect"))
    )
    (net (code "72") (name "unconnected-(U16-DDBUS7-Pad59)") (class "Default")
      (node (ref "U16") (pin "59") (pinfunction "DDBUS7_59") (pintype "passive+no_connect"))
    )
    (net (code "73") (name "unconnected-(U16-~{PWREN}-Pad60)") (class "Default")
      (node (ref "U16") (pin "60") (pinfunction "~{PWREN}_60") (pintype "passive+no_connect"))
    )
    (net (code "74") (name "unconnected-(U16-~{SUSPEND}-Pad36)") (class "Default")
      (node (ref "U16") (pin "36") (pinfunction "~{SUSPEND}_36") (pintype "passive+no_connect"))
    )
  )
)
